# BreaV4.net
KiCad netlist of a schematic drawn in EAGLE
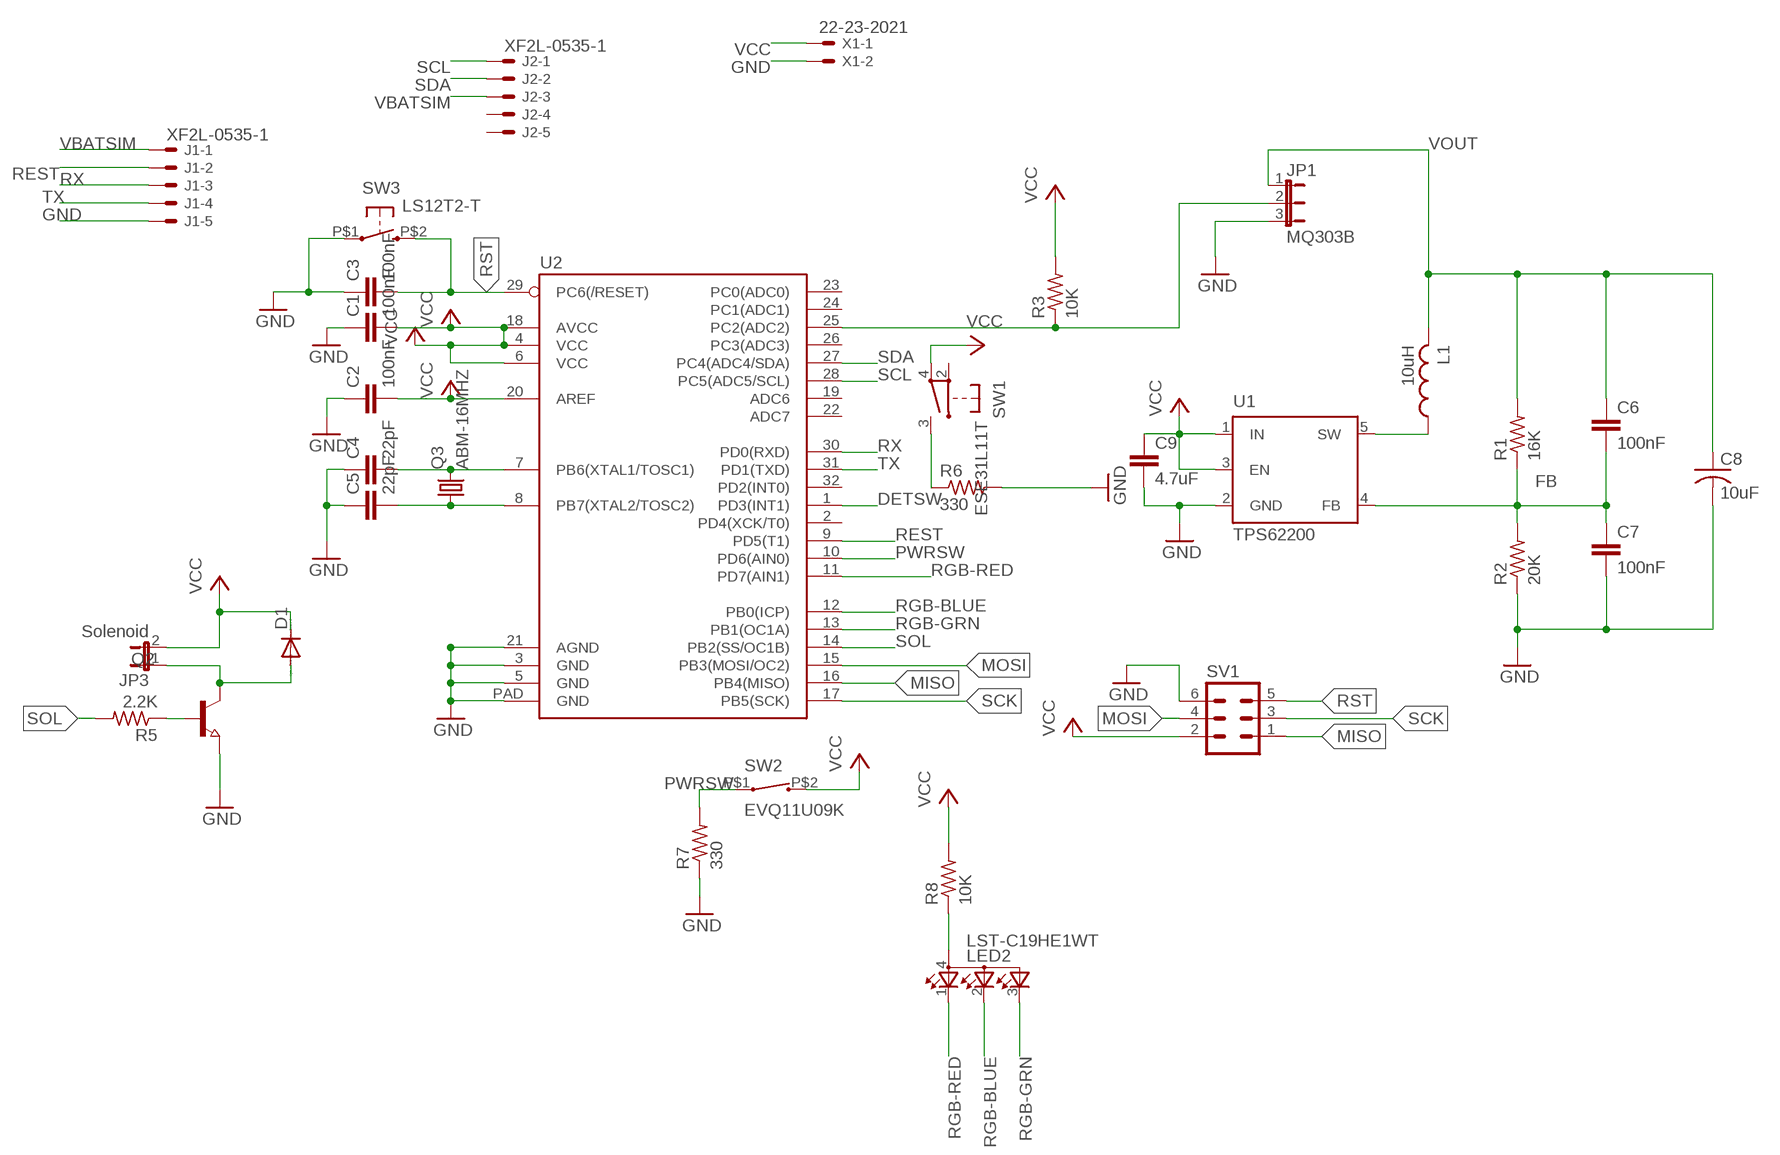
[diagram p0: schematic, sheet 1]

(export (version "E")
  (design (tool "Eeschema 10.0.6"))
  (components
    (comp (ref "C1")
      (value "100nF")
      (footprint "eagle-import:C0603")
      (libsource (lib "eagle-import") (part "C-EUC0603"))
    )
    (comp (ref "C2")
      (value "100nF")
      (footprint "eagle-import:C0603")
      (libsource (lib "eagle-import") (part "C-EUC0603"))
    )
    (comp (ref "C3")
      (value "100nF")
      (footprint "eagle-import:C0603")
      (libsource (lib "eagle-import") (part "C-EUC0603"))
    )
    (comp (ref "C4")
      (value "22pF")
      (footprint "eagle-import:C0603")
      (libsource (lib "eagle-import") (part "C-EUC0603"))
    )
    (comp (ref "C5")
      (value "22pF")
      (footprint "eagle-import:C0603")
      (libsource (lib "eagle-import") (part "C-EUC0603"))
    )
    (comp (ref "C6")
      (value "100nF")
      (footprint "eagle-import:C0402")
      (libsource (lib "eagle-import") (part "C-EUC0402"))
    )
    (comp (ref "C7")
      (value "100nF")
      (footprint "eagle-import:C0402")
      (libsource (lib "eagle-import") (part "C-EUC0402"))
    )
    (comp (ref "C8")
      (value "10uF")
      (footprint "eagle-import:C0805K")
      (libsource (lib "eagle-import") (part "C-USC0805K"))
    )
    (comp (ref "C9")
      (value "4.7uF")
      (footprint "eagle-import:C0402")
      (libsource (lib "eagle-import") (part "C-EUC0402"))
    )
    (comp (ref "D1")
      (value "DIODE-SOD123")
      (footprint "eagle-import:SOD123")
      (libsource (lib "eagle-import") (part "DIODE-SOD123"))
    )
    (comp (ref "J1")
      (value "XF2L-0535-1")
      (footprint "eagle-import:XF2L-0535-1")
      (libsource (lib "eagle-import") (part "XF2-05?35-1L"))
    )
    (comp (ref "J2")
      (value "XF2L-0535-1")
      (footprint "eagle-import:XF2L-0535-1")
      (libsource (lib "eagle-import") (part "XF2-05?35-1L"))
    )
    (comp (ref "JP1")
      (value "MQ303B")
      (footprint "eagle-import:JP2")
      (libsource (lib "eagle-import") (part "JP2E"))
    )
    (comp (ref "JP3")
      (value "Solenoid")
      (footprint "eagle-import:JP1")
      (libsource (lib "eagle-import") (part "JP1E"))
    )
    (comp (ref "L1")
      (value "10uH")
      (footprint "eagle-import:L2825P")
      (libsource (lib "eagle-import") (part "L-USL2825P"))
    )
    (comp (ref "LED2")
      (value "LST-C19HE1WT")
      (footprint "eagle-import:LST-C19HE1WT")
      (libsource (lib "eagle-import") (part "LST-C19HE1WT"))
    )
    (comp (ref "Q2")
      (value "NPN-TRANSISTOR_SOT23")
      (footprint "eagle-import:SOT23")
      (libsource (lib "eagle-import") (part "NPN-TRANSISTOR_SOT23"))
    )
    (comp (ref "Q3")
      (value "ABM-16MHZ")
      (footprint "eagle-import:ABM-16MHZ")
      (libsource (lib "eagle-import") (part "ABM-16MHZ"))
    )
    (comp (ref "R1")
      (value "16K")
      (footprint "eagle-import:R0402")
      (libsource (lib "eagle-import") (part "R-US_R0402"))
    )
    (comp (ref "R2")
      (value "20K")
      (footprint "eagle-import:R0402")
      (libsource (lib "eagle-import") (part "R-US_R0402"))
    )
    (comp (ref "R3")
      (value "10K")
      (footprint "eagle-import:R0402")
      (libsource (lib "eagle-import") (part "R-US_R0402"))
    )
    (comp (ref "R5")
      (value "2.2K")
      (footprint "eagle-import:R0402")
      (libsource (lib "eagle-import") (part "R-US_R0402"))
    )
    (comp (ref "R6")
      (value "330")
      (footprint "eagle-import:R0402")
      (libsource (lib "eagle-import") (part "R-US_R0402"))
    )
    (comp (ref "R7")
      (value "330")
      (footprint "eagle-import:R0402")
      (libsource (lib "eagle-import") (part "R-US_R0402"))
    )
    (comp (ref "R8")
      (value "10K")
      (footprint "eagle-import:R0402")
      (libsource (lib "eagle-import") (part "R-US_R0402"))
    )
    (comp (ref "SV1")
      (value "MA03-2")
      (footprint "eagle-import:MA03-2")
      (libsource (lib "eagle-import") (part "MA03-2"))
    )
    (comp (ref "SW1")
      (value "ESE31L11T")
      (footprint "eagle-import:SWITCH")
      (libsource (lib "eagle-import") (part "ESE31L11T"))
    )
    (comp (ref "SW2")
      (value "EVQ11U09K")
      (footprint "eagle-import:EVQ11U-09K")
      (libsource (lib "eagle-import") (part "EVQ11U09K"))
    )
    (comp (ref "SW3")
      (value "LS12T2-T")
      (footprint "eagle-import:LS12T2-T")
      (libsource (lib "eagle-import") (part "LS12T2-T"))
    )
    (comp (ref "U1")
      (value "TPS62200")
      (footprint "eagle-import:TPS62200")
      (libsource (lib "eagle-import") (part "TPS62200"))
    )
    (comp (ref "U2")
      (value "ATMEGA328P_MLFMLF32")
      (footprint "eagle-import:MLF32-PAD")
      (libsource (lib "eagle-import") (part "ATMEGA328P_MLFMLF32"))
    )
    (comp (ref "X1")
      (value "22-23-2021")
      (footprint "eagle-import:22-23-2021")
      (fields (field (name "MF") "MOLEX"))
      (libsource (lib "eagle-import") (part "22-23-2021"))
    )
  )
  (nets
    (net (code "1") (name "/DETSW") (class "Default")
      (node (ref "R6") (pin "1") (pinfunction "1_1") (pintype "passive"))
      (node (ref "SW1") (pin "3") (pinfunction "1_3") (pintype "passive"))
      (node (ref "U2") (pin "1") (pinfunction "PD3(INT1)_1") (pintype "bidirectional"))
    )
    (net (code "2") (name "/FB") (class "Default")
      (node (ref "C6") (pin "2") (pinfunction "2_2") (pintype "passive"))
      (node (ref "C7") (pin "1") (pinfunction "1_1") (pintype "passive"))
      (node (ref "R1") (pin "1") (pinfunction "1_1") (pintype "passive"))
      (node (ref "R2") (pin "2") (pinfunction "2_2") (pintype "passive"))
      (node (ref "U1") (pin "4") (pinfunction "FB_4") (pintype "passive"))
    )
    (net (code "3") (name "/PWRSW") (class "Default")
      (node (ref "R7") (pin "2") (pinfunction "2_2") (pintype "passive"))
      (node (ref "SW2") (pin "P$1") (pinfunction "1_P$1") (pintype "passive"))
      (node (ref "U2") (pin "10") (pinfunction "PD6(AIN0)_10") (pintype "bidirectional"))
    )
    (net (code "4") (name "/REST") (class "Default")
      (node (ref "J1") (pin "2") (pinfunction "MS_2") (pintype "passive"))
      (node (ref "U2") (pin "9") (pinfunction "PD5(T1)_9") (pintype "bidirectional"))
    )
    (net (code "5") (name "/RGB-BLUE") (class "Default")
      (node (ref "LED2") (pin "2") (pinfunction "CGREEN_2") (pintype "passive"))
      (node (ref "U2") (pin "12") (pinfunction "PB0(ICP)_12") (pintype "bidirectional"))
    )
    (net (code "6") (name "/RGB-GRN") (class "Default")
      (node (ref "LED2") (pin "3") (pinfunction "CBLUE_3") (pintype "passive"))
      (node (ref "U2") (pin "13") (pinfunction "PB1(OC1A)_13") (pintype "bidirectional"))
    )
    (net (code "7") (name "/RGB-RED") (class "Default")
      (node (ref "LED2") (pin "1") (pinfunction "CRED_1") (pintype "passive"))
      (node (ref "U2") (pin "11") (pinfunction "PD7(AIN1)_11") (pintype "bidirectional"))
    )
    (net (code "8") (name "/RX") (class "Default")
      (node (ref "J1") (pin "3") (pinfunction "MS_3") (pintype "passive"))
      (node (ref "U2") (pin "30") (pinfunction "PD0(RXD)_30") (pintype "bidirectional"))
    )
    (net (code "9") (name "/SCL") (class "Default")
      (node (ref "J2") (pin "1") (pinfunction "MSV_1") (pintype "passive"))
      (node (ref "U2") (pin "28") (pinfunction "PC5(ADC5/SCL)_28") (pintype "bidirectional"))
    )
    (net (code "10") (name "/SDA") (class "Default")
      (node (ref "J2") (pin "2") (pinfunction "MS_2") (pintype "passive"))
      (node (ref "U2") (pin "27") (pinfunction "PC4(ADC4/SDA)_27") (pintype "bidirectional"))
    )
    (net (code "11") (name "/TX") (class "Default")
      (node (ref "J1") (pin "4") (pinfunction "MS_4") (pintype "passive"))
      (node (ref "U2") (pin "31") (pinfunction "PD1(TXD)_31") (pintype "bidirectional"))
    )
    (net (code "12") (name "/VBATSIM") (class "Default")
      (node (ref "J1") (pin "1") (pinfunction "MSV_1") (pintype "passive"))
      (node (ref "J2") (pin "3") (pinfunction "MS_3") (pintype "passive"))
    )
    (net (code "13") (name "/VOUT") (class "Default")
      (node (ref "C6") (pin "1") (pinfunction "1_1") (pintype "passive"))
      (node (ref "C8") (pin "1") (pinfunction "1_1") (pintype "passive"))
      (node (ref "JP1") (pin "1") (pinfunction "1_1") (pintype "passive"))
      (node (ref "L1") (pin "2") (pinfunction "2_2") (pintype "passive"))
      (node (ref "R1") (pin "2") (pinfunction "2_2") (pintype "passive"))
    )
    (net (code "14") (name "GND") (class "Default")
      (node (ref "C1") (pin "1") (pinfunction "1_1") (pintype "passive"))
      (node (ref "C2") (pin "1") (pinfunction "1_1") (pintype "passive"))
      (node (ref "C3") (pin "1") (pinfunction "1_1") (pintype "passive"))
      (node (ref "C4") (pin "1") (pinfunction "1_1") (pintype "passive"))
      (node (ref "C5") (pin "1") (pinfunction "1_1") (pintype "passive"))
      (node (ref "C7") (pin "2") (pinfunction "2_2") (pintype "passive"))
      (node (ref "C8") (pin "2") (pinfunction "2_2") (pintype "passive"))
      (node (ref "C9") (pin "2") (pinfunction "2_2") (pintype "passive"))
      (node (ref "J1") (pin "5") (pinfunction "MS_5") (pintype "passive"))
      (node (ref "JP1") (pin "3") (pinfunction "3_3") (pintype "passive"))
      (node (ref "Q2") (pin "2") (pinfunction "E_2") (pintype "passive"))
      (node (ref "R2") (pin "1") (pinfunction "1_1") (pintype "passive"))
      (node (ref "R6") (pin "2") (pinfunction "2_2") (pintype "passive"))
      (node (ref "R7") (pin "1") (pinfunction "1_1") (pintype "passive"))
      (node (ref "SV1") (pin "6") (pinfunction "MISO_6") (pintype "passive"))
      (node (ref "SW3") (pin "P$1") (pinfunction "S1_P$1") (pintype "passive"))
      (node (ref "U1") (pin "2") (pinfunction "GND_2") (pintype "power_in"))
      (node (ref "U2") (pin "21") (pinfunction "AGND_21") (pintype "bidirectional"))
      (node (ref "U2") (pin "3") (pinfunction "GND_3") (pintype "bidirectional"))
      (node (ref "U2") (pin "5") (pinfunction "GND_5") (pintype "bidirectional"))
      (node (ref "U2") (pin "PAD") (pinfunction "GND_PAD") (pintype "bidirectional"))
      (node (ref "X1") (pin "2") (pinfunction "S_2") (pintype "passive"))
    )
    (net (code "15") (name "MISO") (class "Default")
      (node (ref "SV1") (pin "1") (pinfunction "1_1") (pintype "passive"))
      (node (ref "U2") (pin "16") (pinfunction "PB4(MISO)_16") (pintype "bidirectional"))
    )
    (net (code "16") (name "MOSI") (class "Default")
      (node (ref "SV1") (pin "4") (pinfunction "4_4") (pintype "passive"))
      (node (ref "U2") (pin "15") (pinfunction "PB3(MOSI/OC2)_15") (pintype "bidirectional"))
    )
    (net (code "17") (name "Net-(LED2-A)") (class "Default")
      (node (ref "LED2") (pin "4") (pinfunction "A_4") (pintype "passive"))
      (node (ref "R8") (pin "1") (pinfunction "1_1") (pintype "passive"))
    )
    (net (code "18") (name "Net-(Q2-B)") (class "Default")
      (node (ref "Q2") (pin "1") (pinfunction "B_1") (pintype "passive"))
      (node (ref "R5") (pin "1") (pinfunction "1_1") (pintype "passive"))
    )
    (net (code "19") (name "Net-(Q2-C)") (class "Default")
      (node (ref "D1") (pin "A") (pinfunction "A_A") (pintype "passive"))
      (node (ref "JP3") (pin "1") (pinfunction "1_1") (pintype "passive"))
      (node (ref "Q2") (pin "3") (pinfunction "C_3") (pintype "passive"))
    )
    (net (code "20") (name "Net-(Q3-1)") (class "Default")
      (node (ref "C5") (pin "2") (pinfunction "2_2") (pintype "passive"))
      (node (ref "Q3") (pin "P$1") (pinfunction "1_P$1") (pintype "passive"))
      (node (ref "U2") (pin "8") (pinfunction "PB7(XTAL2/TOSC2)_8") (pintype "bidirectional"))
    )
    (net (code "21") (name "Net-(Q3-2)") (class "Default")
      (node (ref "C4") (pin "2") (pinfunction "2_2") (pintype "passive"))
      (node (ref "Q3") (pin "P$2") (pinfunction "2_P$2") (pintype "passive"))
      (node (ref "U2") (pin "7") (pinfunction "PB6(XTAL1/TOSC1)_7") (pintype "bidirectional"))
    )
    (net (code "22") (name "Net-(U1-SW)") (class "Default")
      (node (ref "L1") (pin "1") (pinfunction "1_1") (pintype "passive"))
      (node (ref "U1") (pin "5") (pinfunction "SW_5") (pintype "passive"))
    )
    (net (code "23") (name "Net-(U2-PC2(ADC2))") (class "Default")
      (node (ref "JP1") (pin "2") (pinfunction "2_2") (pintype "passive"))
      (node (ref "R3") (pin "1") (pinfunction "1_1") (pintype "passive"))
      (node (ref "U2") (pin "25") (pinfunction "PC2(ADC2)_25") (pintype "bidirectional"))
    )
    (net (code "24") (name "RST") (class "Default")
      (node (ref "C3") (pin "2") (pinfunction "2_2") (pintype "passive"))
      (node (ref "SV1") (pin "5") (pinfunction "VTG_5") (pintype "passive"))
      (node (ref "SW3") (pin "P$2") (pinfunction "S2_P$2") (pintype "passive"))
      (node (ref "U2") (pin "29") (pinfunction "PC6(/RESET)_29") (pintype "bidirectional"))
    )
    (net (code "25") (name "SCK") (class "Default")
      (node (ref "SV1") (pin "3") (pinfunction "3_3") (pintype "passive"))
      (node (ref "U2") (pin "17") (pinfunction "PB5(SCK)_17") (pintype "bidirectional"))
    )
    (net (code "26") (name "SOL") (class "Default")
      (node (ref "R5") (pin "2") (pinfunction "2_2") (pintype "passive"))
      (node (ref "U2") (pin "14") (pinfunction "PB2(SS/OC1B)_14") (pintype "bidirectional"))
    )
    (net (code "27") (name "VCC") (class "Default")
      (node (ref "C1") (pin "2") (pinfunction "2_2") (pintype "passive"))
      (node (ref "C2") (pin "2") (pinfunction "2_2") (pintype "passive"))
      (node (ref "C9") (pin "1") (pinfunction "1_1") (pintype "passive"))
      (node (ref "D1") (pin "C") (pinfunction "C_C") (pintype "passive"))
      (node (ref "JP3") (pin "2") (pinfunction "2_2") (pintype "passive"))
      (node (ref "R3") (pin "2") (pinfunction "2_2") (pintype "passive"))
      (node (ref "R8") (pin "2") (pinfunction "2_2") (pintype "passive"))
      (node (ref "SV1") (pin "2") (pinfunction "2_2") (pintype "passive"))
      (node (ref "SW1") (pin "4") (pinfunction "C3_4") (pintype "passive"))
      (node (ref "SW2") (pin "P$2") (pinfunction "2_P$2") (pintype "passive"))
      (node (ref "U1") (pin "1") (pinfunction "IN_1") (pintype "input"))
      (node (ref "U1") (pin "3") (pinfunction "EN_3") (pintype "input"))
      (node (ref "U2") (pin "18") (pinfunction "AVCC_18") (pintype "bidirectional"))
      (node (ref "U2") (pin "20") (pinfunction "AREF_20") (pintype "bidirectional"))
      (node (ref "U2") (pin "4") (pinfunction "VCC_4") (pintype "bidirectional"))
      (node (ref "U2") (pin "6") (pinfunction "VCC_6") (pintype "bidirectional"))
      (node (ref "X1") (pin "1") (pinfunction "S_1") (pintype "passive"))
    )
    (net (code "28") (name "unconnected-(J2D-MS-Pad4)") (class "Default")
      (node (ref "J2") (pin "4") (pinfunction "MS_4") (pintype "passive"))
    )
    (net (code "29") (name "unconnected-(J2E-MS-Pad5)") (class "Default")
      (node (ref "J2") (pin "5") (pinfunction "MS_5") (pintype "passive"))
    )
    (net (code "30") (name "unconnected-(SW1-C2-Pad2)") (class "Default")
      (node (ref "SW1") (pin "2") (pinfunction "C2_2") (pintype "passive"))
    )
    (net (code "31") (name "unconnected-(U2-ADC6-Pad19)") (class "Default")
      (node (ref "U2") (pin "19") (pinfunction "ADC6_19") (pintype "bidirectional"))
    )
    (net (code "32") (name "unconnected-(U2-ADC7-Pad22)") (class "Default")
      (node (ref "U2") (pin "22") (pinfunction "ADC7_22") (pintype "bidirectional"))
    )
    (net (code "33") (name "unconnected-(U2-PC0(ADC0)-Pad23)") (class "Default")
      (node (ref "U2") (pin "23") (pinfunction "PC0(ADC0)_23") (pintype "bidirectional"))
    )
    (net (code "34") (name "unconnected-(U2-PC1(ADC1)-Pad24)") (class "Default")
      (node (ref "U2") (pin "24") (pinfunction "PC1(ADC1)_24") (pintype "bidirectional"))
    )
    (net (code "35") (name "unconnected-(U2-PC3(ADC3)-Pad26)") (class "Default")
      (node (ref "U2") (pin "26") (pinfunction "PC3(ADC3)_26") (pintype "bidirectional"))
    )
    (net (code "36") (name "unconnected-(U2-PD2(INT0)-Pad32)") (class "Default")
      (node (ref "U2") (pin "32") (pinfunction "PD2(INT0)_32") (pintype "bidirectional"))
    )
    (net (code "37") (name "unconnected-(U2-PD4(XCK{slash}T0)-Pad2)") (class "Default")
      (node (ref "U2") (pin "2") (pinfunction "PD4(XCK/T0)_2") (pintype "bidirectional"))
    )
  )
)
